# SD_NRF_RC522_W5500.net
KiCad netlist of a schematic drawn in Altium Designer
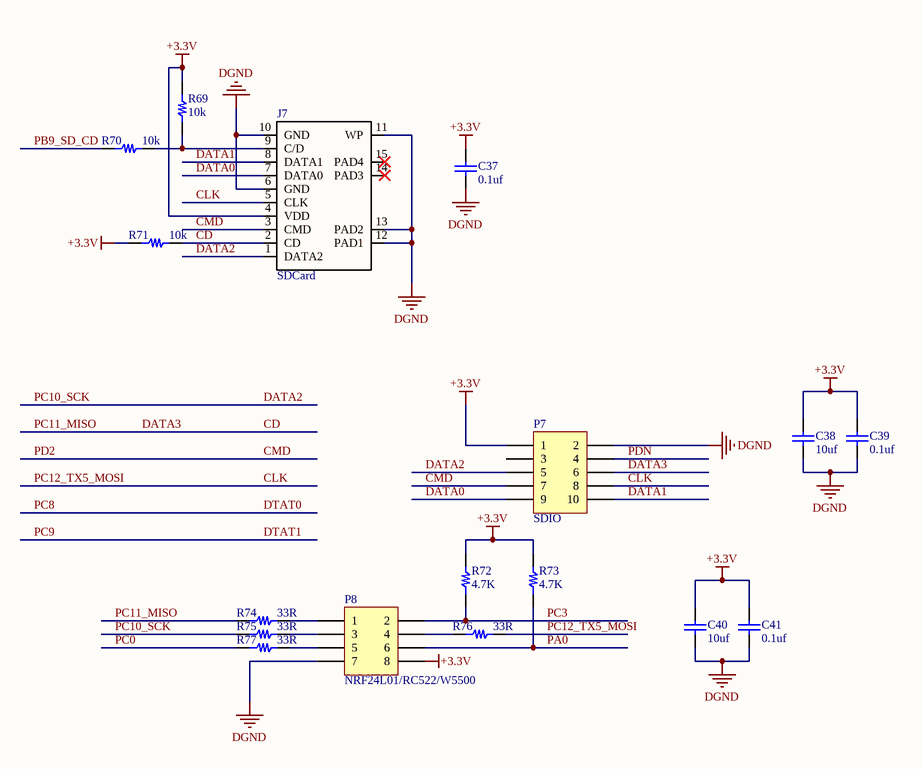
[diagram p0: SD_NRF_RC522_W5500.SchDoc]

(export (version "E")
  (design (tool "Eeschema 10.0.6"))
  (components
    (comp (ref "C37")
      (value "0.1uf")
      (footprint "0805C")
      (description "贴片电容")
      (fields (field (name "PUBLISHER") "Altium Limited"))
      (libsource (lib "Device_CHT") (part "Cap"))
    )
    (comp (ref "C38")
      (value "10uf")
      (footprint "0805C")
      (description "贴片电容")
      (fields (field (name "PUBLISHER") "Altium Limited"))
      (libsource (lib "Device_CHT") (part "Cap"))
    )
    (comp (ref "C39")
      (value "0.1uf")
      (footprint "0805C")
      (description "贴片电容")
      (fields (field (name "PUBLISHER") "Altium Limited"))
      (libsource (lib "Device_CHT") (part "Cap"))
    )
    (comp (ref "C40")
      (value "10uf")
      (footprint "0805C")
      (description "贴片电容")
      (fields (field (name "PUBLISHER") "Altium Limited"))
      (libsource (lib "Device_CHT") (part "Cap"))
    )
    (comp (ref "C41")
      (value "0.1uf")
      (footprint "0805C")
      (description "贴片电容")
      (fields (field (name "PUBLISHER") "Altium Limited"))
      (libsource (lib "Device_CHT") (part "Cap"))
    )
    (comp (ref "J7")
      (value "SDCard")
      (footprint "TFP09-2-12B")
      (description "带弹簧的SD-TF卡座")
      (libsource (lib "Connector_Veiko") (part "sd_card_tf_0"))
    )
    (comp (ref "P7")
      (value "SDIO")
      (footprint "HDR2X5-2.54MM")
      (description "Header, 5-Pin, Dual row")
      (fields (field (name "PUBLISHER") "Altium Limited"))
      (libsource (lib "Connector_Veiko") (part "CON5X2"))
    )
    (comp (ref "P8")
      (value "NRF24L01/RC522/W5500")
      (footprint "HDR2X4-2.54MM")
      (description "Header, 4-Pin, Dual row")
      (fields (field (name "PUBLISHER") "Altium Limited"))
      (libsource (lib "Connector_Veiko") (part "CON4X2"))
    )
    (comp (ref "R69")
      (value "10k")
      (footprint "0805_small")
      (description "电阻")
      (fields (field (name "PUBLISHER") "Altium Limited"))
      (libsource (lib "Device_CHT") (part "Res"))
    )
    (comp (ref "R70")
      (value "10k")
      (footprint "0805_small")
      (description "电阻")
      (fields (field (name "PUBLISHER") "Altium Limited"))
      (libsource (lib "Device_CHT") (part "Res"))
    )
    (comp (ref "R71")
      (value "10k")
      (footprint "0805_small")
      (description "电阻")
      (fields (field (name "PUBLISHER") "Altium Limited"))
      (libsource (lib "Device_CHT") (part "Res"))
    )
    (comp (ref "R72")
      (value "4.7K")
      (footprint "0805_small")
      (description "电阻")
      (fields (field (name "PUBLISHER") "Altium Limited"))
      (libsource (lib "Device_CHT") (part "Res"))
    )
    (comp (ref "R73")
      (value "4.7K")
      (footprint "0805_small")
      (description "电阻")
      (fields (field (name "PUBLISHER") "Altium Limited"))
      (libsource (lib "Device_CHT") (part "Res"))
    )
    (comp (ref "R74")
      (value "33R")
      (footprint "0805_small")
      (description "电阻")
      (fields (field (name "PUBLISHER") "Altium Limited"))
      (libsource (lib "Device_CHT") (part "Res"))
    )
    (comp (ref "R75")
      (value "33R")
      (footprint "0805_small")
      (description "电阻")
      (fields (field (name "PUBLISHER") "Altium Limited"))
      (libsource (lib "Device_CHT") (part "Res"))
    )
    (comp (ref "R76")
      (value "33R")
      (footprint "0805_small")
      (description "电阻")
      (fields (field (name "PUBLISHER") "Altium Limited"))
      (libsource (lib "Device_CHT") (part "Res"))
    )
    (comp (ref "R77")
      (value "33R")
      (footprint "0805_small")
      (description "电阻")
      (fields (field (name "PUBLISHER") "Altium Limited"))
      (libsource (lib "Device_CHT") (part "Res"))
    )
  )
  (nets
    (net (code "1") (name "+3.3V") (class "Default")
      (node (ref "C37") (pin "1") (pinfunction "1_1") (pintype "passive"))
      (node (ref "C38") (pin "1") (pinfunction "1_1") (pintype "passive"))
      (node (ref "C39") (pin "1") (pinfunction "1_1") (pintype "passive"))
      (node (ref "C40") (pin "1") (pinfunction "1_1") (pintype "passive"))
      (node (ref "C41") (pin "1") (pinfunction "1_1") (pintype "passive"))
      (node (ref "J7") (pin "4") (pinfunction "VDD_4") (pintype "passive"))
      (node (ref "P7") (pin "1") (pinfunction "1_1") (pintype "passive"))
      (node (ref "P8") (pin "8") (pinfunction "8_8") (pintype "passive"))
      (node (ref "R69") (pin "1") (pinfunction "1_1") (pintype "passive"))
      (node (ref "R71") (pin "1") (pinfunction "1_1") (pintype "passive"))
      (node (ref "R72") (pin "2") (pinfunction "2_2") (pintype "passive"))
      (node (ref "R73") (pin "2") (pinfunction "2_2") (pintype "passive"))
    )
    (net (code "2") (name "/CD") (class "Default")
      (node (ref "J7") (pin "2") (pinfunction "CD_2") (pintype "passive"))
      (node (ref "P7") (pin "6") (pinfunction "6_6") (pintype "passive"))
      (node (ref "R71") (pin "2") (pinfunction "2_2") (pintype "passive"))
      (node (ref "R74") (pin "1") (pinfunction "1_1") (pintype "passive"))
    )
    (net (code "3") (name "/CLK") (class "Default")
      (node (ref "J7") (pin "5") (pinfunction "CLK_5") (pintype "passive"))
      (node (ref "P7") (pin "8") (pinfunction "8_8") (pintype "passive"))
      (node (ref "R76") (pin "2") (pinfunction "2_2") (pintype "passive"))
    )
    (net (code "4") (name "/CMD") (class "Default")
      (node (ref "J7") (pin "3") (pinfunction "CMD_3") (pintype "passive"))
      (node (ref "P7") (pin "7") (pinfunction "7_7") (pintype "passive"))
    )
    (net (code "5") (name "/DATA0") (class "Default")
      (node (ref "J7") (pin "7") (pinfunction "DATA0_7") (pintype "passive"))
      (node (ref "P7") (pin "9") (pinfunction "9_9") (pintype "passive"))
    )
    (net (code "6") (name "/DATA1") (class "Default")
      (node (ref "J7") (pin "8") (pinfunction "DATA1_8") (pintype "passive"))
      (node (ref "P7") (pin "10") (pinfunction "10_10") (pintype "passive"))
    )
    (net (code "7") (name "/DATA2") (class "Default")
      (node (ref "J7") (pin "1") (pinfunction "DATA2_1") (pintype "passive"))
      (node (ref "P7") (pin "5") (pinfunction "5_5") (pintype "passive"))
      (node (ref "R75") (pin "1") (pinfunction "1_1") (pintype "passive"))
    )
    (net (code "10") (name "/PA0") (class "Default")
      (node (ref "P8") (pin "6") (pinfunction "6_6") (pintype "passive"))
      (node (ref "R73") (pin "1") (pinfunction "1_1") (pintype "passive"))
    )
    (net (code "11") (name "/PB9_SD_CD") (class "Default")
      (node (ref "R70") (pin "1") (pinfunction "1_1") (pintype "passive"))
    )
    (net (code "12") (name "/PC0") (class "Default")
      (node (ref "R77") (pin "1") (pinfunction "1_1") (pintype "passive"))
    )
    (net (code "13") (name "/PC3") (class "Default")
      (node (ref "P8") (pin "2") (pinfunction "2_2") (pintype "passive"))
      (node (ref "R72") (pin "1") (pinfunction "1_1") (pintype "passive"))
    )
    (net (code "14") (name "/PDN") (class "Default")
      (node (ref "P7") (pin "4") (pinfunction "4_4") (pintype "passive"))
    )
    (net (code "15") (name "DGND") (class "Default")
      (node (ref "C37") (pin "2") (pinfunction "2_2") (pintype "passive"))
      (node (ref "C38") (pin "2") (pinfunction "2_2") (pintype "passive"))
      (node (ref "C39") (pin "2") (pinfunction "2_2") (pintype "passive"))
      (node (ref "C40") (pin "2") (pinfunction "2_2") (pintype "passive"))
      (node (ref "C41") (pin "2") (pinfunction "2_2") (pintype "passive"))
      (node (ref "J7") (pin "10") (pinfunction "GND_10") (pintype "passive"))
      (node (ref "J7") (pin "11") (pinfunction "WP_11") (pintype "passive"))
      (node (ref "J7") (pin "12") (pinfunction "PAD1_12") (pintype "passive"))
      (node (ref "J7") (pin "13") (pinfunction "PAD2_13") (pintype "passive"))
      (node (ref "J7") (pin "6") (pinfunction "GND_6") (pintype "passive"))
      (node (ref "P7") (pin "2") (pinfunction "2_2") (pintype "passive"))
      (node (ref "P8") (pin "7") (pinfunction "7_7") (pintype "passive"))
    )
    (net (code "16") (name "Net-(J7-C{slash}D)") (class "Default")
      (node (ref "J7") (pin "9") (pinfunction "C/D_9") (pintype "passive"))
      (node (ref "R69") (pin "2") (pinfunction "2_2") (pintype "passive"))
      (node (ref "R70") (pin "2") (pinfunction "2_2") (pintype "passive"))
    )
    (net (code "17") (name "Net-(P8-Pad1)") (class "Default")
      (node (ref "P8") (pin "1") (pinfunction "1_1") (pintype "passive"))
      (node (ref "R74") (pin "2") (pinfunction "2_2") (pintype "passive"))
    )
    (net (code "18") (name "Net-(P8-Pad3)") (class "Default")
      (node (ref "P8") (pin "3") (pinfunction "3_3") (pintype "passive"))
      (node (ref "R75") (pin "2") (pinfunction "2_2") (pintype "passive"))
    )
    (net (code "19") (name "Net-(P8-Pad4)") (class "Default")
      (node (ref "P8") (pin "4") (pinfunction "4_4") (pintype "passive"))
      (node (ref "R76") (pin "1") (pinfunction "1_1") (pintype "passive"))
    )
    (net (code "20") (name "Net-(P8-Pad5)") (class "Default")
      (node (ref "P8") (pin "5") (pinfunction "5_5") (pintype "passive"))
      (node (ref "R77") (pin "2") (pinfunction "2_2") (pintype "passive"))
    )
    (net (code "21") (name "unconnected-(J7-PAD3-Pad14)") (class "Default")
      (node (ref "J7") (pin "14") (pinfunction "PAD3_14") (pintype "passive+no_connect"))
    )
    (net (code "22") (name "unconnected-(J7-PAD4-Pad15)") (class "Default")
      (node (ref "J7") (pin "15") (pinfunction "PAD4_15") (pintype "passive+no_connect"))
    )
    (net (code "23") (name "unconnected-(P7-Pad3)") (class "Default")
      (node (ref "P7") (pin "3") (pinfunction "3_3") (pintype "passive"))
    )
  )
)
